# float.net
KiCad netlist of a schematic drawn in Altium Designer
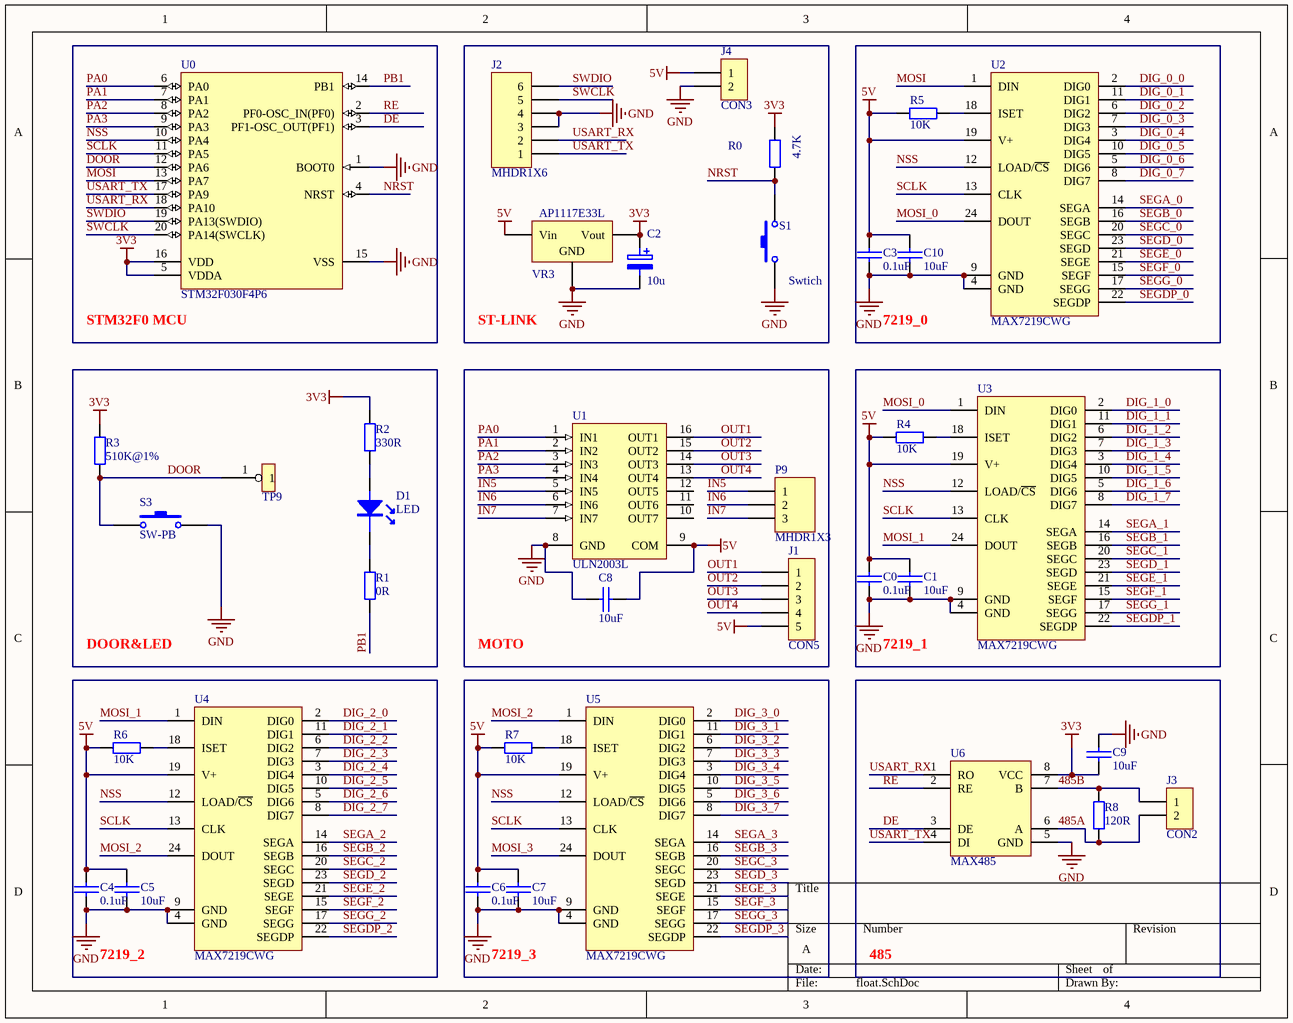
[diagram p0: float.SchDoc]

(export (version "E")
  (design (tool "Eeschema 10.0.6"))
  (components
    (comp (ref "C0")
      (value "0.1uF")
      (footprint "0603C")
      (description "Capacitor")
      (libsource (lib "Miscellaneous Devices") (part "CAP"))
    )
    (comp (ref "C1")
      (value "10uF")
      (footprint "0603C")
      (description "Capacitor")
      (libsource (lib "Miscellaneous Devices") (part "CAP"))
    )
    (comp (ref "C2") (value "10u") (footprint "LC-CASE-B_3528") (libsource (lib "*") (part "ELECTRO2")))
    (comp (ref "C3")
      (value "0.1uF")
      (footprint "0603C")
      (description "Capacitor")
      (libsource (lib "Miscellaneous Devices") (part "CAP"))
    )
    (comp (ref "C4")
      (value "0.1uF")
      (footprint "0603C")
      (description "Capacitor")
      (libsource (lib "Miscellaneous Devices") (part "CAP"))
    )
    (comp (ref "C5")
      (value "10uF")
      (footprint "0603C")
      (description "Capacitor")
      (libsource (lib "Miscellaneous Devices") (part "CAP"))
    )
    (comp (ref "C6")
      (value "0.1uF")
      (footprint "0603C")
      (description "Capacitor")
      (libsource (lib "Miscellaneous Devices") (part "CAP"))
    )
    (comp (ref "C7")
      (value "10uF")
      (footprint "0603C")
      (description "Capacitor")
      (libsource (lib "Miscellaneous Devices") (part "CAP"))
    )
    (comp (ref "C8")
      (value "10uF")
      (footprint "0603C")
      (description "Capacitor")
      (libsource (lib "Miscellaneous Devices") (part "CAP"))
    )
    (comp (ref "C9")
      (value "10uF")
      (footprint "0603C")
      (description "Capacitor")
      (libsource (lib "Miscellaneous Devices") (part "CAP"))
    )
    (comp (ref "C10")
      (value "10uF")
      (footprint "0603C")
      (description "Capacitor")
      (libsource (lib "Miscellaneous Devices") (part "CAP"))
    )
    (comp (ref "D1")
      (value "LED")
      (footprint "LC-0603_LED_S1")
      (libsource (lib "BASIC Devices") (part "LED"))
    )
    (comp (ref "J1")
      (value "CON5")
      (footprint "HDR1X5")
      (description "Connector")
      (libsource (lib "插件") (part "CON5"))
    )
    (comp (ref "J2")
      (value "MHDR1X6")
      (footprint "Miscellaneous Connectors:HDR1X6")
      (description "Header, 6-Pin")
      (fields (field (name "PUBLISHER") "Altium Limited"))
      (libsource (lib "Miscellaneous Connectors") (part "MHDR1X6"))
    )
    (comp (ref "J3")
      (value "CON2")
      (footprint "HDR1X2")
      (description "Connector")
      (libsource (lib "Miscellaneous Devices") (part "CON2"))
    )
    (comp (ref "J4")
      (value "CON3")
      (footprint "HDR1X2")
      (description "Connector")
      (libsource (lib "Miscellaneous Devices") (part "CON2"))
    )
    (comp (ref "P9")
      (value "MHDR1X3")
      (footprint "HDR1X3")
      (description "Header, 3-Pin")
      (fields (field (name "PUBLISHER") "Altium Limited"))
      (libsource (lib "Miscellaneous Connectors") (part "MHDR1X3"))
    )
    (comp (ref "R0")
      (value "4.7K")
      (footprint "0603R")
      (description "Resistor")
      (fields (field (name "Comment") "RES") (field (name "PUBLISHER") "Altium Limited"))
      (libsource (lib "") (part "Res2_1"))
    )
    (comp (ref "R1")
      (value "0R")
      (footprint "0603R")
      (description "贴片电阻")
      (fields (field (name "Comment") "Res1") (field (name "PUBLISHER") "Altium Limited"))
      (libsource (lib "Fszhang") (part "Res1"))
    )
    (comp (ref "R2")
      (value "330R")
      (footprint "0603R")
      (description "贴片电阻")
      (fields (field (name "Comment") "Res1") (field (name "PUBLISHER") "Altium Limited"))
      (libsource (lib "Fszhang") (part "Res1"))
    )
    (comp (ref "R3")
      (value "510K@1%")
      (footprint "0603R")
      (description "Resistor")
      (fields (field (name "Comment") "Res") (field (name "PUBLISHER") "Altium Limited"))
      (libsource (lib "") (part "Res2_3"))
    )
    (comp (ref "R4")
      (value "10K")
      (footprint "0603R")
      (description "Resistor")
      (fields (field (name "Comment") "RES") (field (name "PUBLISHER") "Altium Limited"))
      (libsource (lib "Miscellaneous Devices") (part "Res2"))
    )
    (comp (ref "R5")
      (value "10K")
      (footprint "0603R")
      (description "Resistor")
      (fields (field (name "Comment") "RES") (field (name "PUBLISHER") "Altium Limited"))
      (libsource (lib "Miscellaneous Devices") (part "Res2"))
    )
    (comp (ref "R6")
      (value "10K")
      (footprint "0603R")
      (description "Resistor")
      (fields (field (name "Comment") "RES") (field (name "PUBLISHER") "Altium Limited"))
      (libsource (lib "Miscellaneous Devices") (part "Res2"))
    )
    (comp (ref "R7")
      (value "10K")
      (footprint "0603R")
      (description "Resistor")
      (fields (field (name "Comment") "RES") (field (name "PUBLISHER") "Altium Limited"))
      (libsource (lib "Miscellaneous Devices") (part "Res2"))
    )
    (comp (ref "R8")
      (value "120R")
      (footprint "0603R")
      (description "Resistor")
      (fields (field (name "Comment") "RES") (field (name "PUBLISHER") "Altium Limited"))
      (libsource (lib "") (part "Res2_2"))
    )
    (comp (ref "S1")
      (value "Swtich")
      (footprint "KEY_M")
      (description "Switch")
      (fields (field (name "PUBLISHER") "Altium Limited"))
      (libsource (lib "connectors") (part "SW-PB"))
    )
    (comp (ref "S3")
      (value "SW-PB")
      (footprint "reed_switch")
      (description "Switch")
      (fields (field (name "PUBLISHER") "Altium Limited"))
      (libsource (lib "connectors") (part "SW-PB"))
    )
    (comp (ref "TP9") (value "TP") (footprint "TP1") (libsource (lib "devices") (part "TP")))
    (comp (ref "U0")
      (value "STM32F030F4P6")
      (footprint "STM-TSSOP20_L")
      (libsource (lib "STMicroelectronics STM32 F0") (part "STM32F030F4P6"))
    )
    (comp (ref "U1")
      (value "ULN2003L")
      (footprint "NSO16_M")
      (description "驱动芯片")
      (fields (field (name "PUBLISHER") "Altium Limited"))
      (libsource (lib "Fszhang") (part "ULN2003L"))
    )
    (comp (ref "U2")
      (value "MAX7219CWG")
      (footprint "SO-24W")
      (description "CI-MAX7219CWG")
      (libsource (lib "IC(1)") (part "MAX7219CWG"))
    )
    (comp (ref "U3")
      (value "MAX7219CWG")
      (footprint "SO-24W")
      (description "CI-MAX7219CWG")
      (libsource (lib "IC(1)") (part "MAX7219CWG"))
    )
    (comp (ref "U4")
      (value "MAX7219CWG")
      (footprint "SO-24W")
      (description "CI-MAX7219CWG")
      (libsource (lib "IC(1)") (part "MAX7219CWG"))
    )
    (comp (ref "U5")
      (value "MAX7219CWG")
      (footprint "SO-24W")
      (description "CI-MAX7219CWG")
      (libsource (lib "IC(1)") (part "MAX7219CWG"))
    )
    (comp (ref "U6")
      (value "MAX485")
      (footprint "NSO8_N")
      (description "485总线芯片")
      (libsource (lib "Fszhang") (part "SP3485"))
    )
    (comp (ref "VR3")
      (value "AP1117E33L")
      (footprint "LC-SOT-223")
      (description "Voltage Regulator")
      (fields (field (name "PUBLISHER") "Altium Limited"))
      (libsource (lib "在线监测仪-02") (part "Volt Reg"))
    )
  )
  (nets
    (net (code "1") (name "/485A") (class "Default")
      (node (ref "J3") (pin "2") (pinfunction "2_2") (pintype "passive"))
      (node (ref "R8") (pin "1") (pinfunction "1_1") (pintype "passive"))
      (node (ref "U6") (pin "6") (pinfunction "A_6") (pintype "passive"))
    )
    (net (code "2") (name "/485B") (class "Default")
      (node (ref "J3") (pin "1") (pinfunction "1_1") (pintype "passive"))
      (node (ref "R8") (pin "2") (pinfunction "2_2") (pintype "passive"))
      (node (ref "U6") (pin "7") (pinfunction "B_7") (pintype "passive"))
    )
    (net (code "3") (name "/DE") (class "Default")
      (node (ref "U0") (pin "3") (pinfunction "PF1-OSC_OUT(PF1)_3") (pintype "bidirectional"))
      (node (ref "U6") (pin "3") (pinfunction "DE_3") (pintype "passive"))
    )
    (net (code "4") (name "/DIG_0_0") (class "Default")
      (node (ref "U2") (pin "2") (pinfunction "DIG0_2") (pintype "passive"))
    )
    (net (code "5") (name "/DIG_0_1") (class "Default")
      (node (ref "U2") (pin "11") (pinfunction "DIG1_11") (pintype "passive"))
    )
    (net (code "6") (name "/DIG_0_2") (class "Default")
      (node (ref "U2") (pin "6") (pinfunction "DIG2_6") (pintype "passive"))
    )
    (net (code "7") (name "/DIG_0_3") (class "Default")
      (node (ref "U2") (pin "7") (pinfunction "DIG3_7") (pintype "passive"))
    )
    (net (code "8") (name "/DIG_0_4") (class "Default")
      (node (ref "U2") (pin "3") (pinfunction "DIG4_3") (pintype "passive"))
    )
    (net (code "9") (name "/DIG_0_5") (class "Default")
      (node (ref "U2") (pin "10") (pinfunction "DIG5_10") (pintype "passive"))
    )
    (net (code "10") (name "/DIG_0_6") (class "Default")
      (node (ref "U2") (pin "5") (pinfunction "DIG6_5") (pintype "passive"))
    )
    (net (code "11") (name "/DIG_0_7") (class "Default")
      (node (ref "U2") (pin "8") (pinfunction "DIG7_8") (pintype "passive"))
    )
    (net (code "12") (name "/DIG_1_0") (class "Default")
      (node (ref "U3") (pin "2") (pinfunction "DIG0_2") (pintype "passive"))
    )
    (net (code "13") (name "/DIG_1_1") (class "Default")
      (node (ref "U3") (pin "11") (pinfunction "DIG1_11") (pintype "passive"))
    )
    (net (code "14") (name "/DIG_1_2") (class "Default")
      (node (ref "U3") (pin "6") (pinfunction "DIG2_6") (pintype "passive"))
    )
    (net (code "15") (name "/DIG_1_3") (class "Default")
      (node (ref "U3") (pin "7") (pinfunction "DIG3_7") (pintype "passive"))
    )
    (net (code "16") (name "/DIG_1_4") (class "Default")
      (node (ref "U3") (pin "3") (pinfunction "DIG4_3") (pintype "passive"))
    )
    (net (code "17") (name "/DIG_1_5") (class "Default")
      (node (ref "U3") (pin "10") (pinfunction "DIG5_10") (pintype "passive"))
    )
    (net (code "18") (name "/DIG_1_6") (class "Default")
      (node (ref "U3") (pin "5") (pinfunction "DIG6_5") (pintype "passive"))
    )
    (net (code "19") (name "/DIG_1_7") (class "Default")
      (node (ref "U3") (pin "8") (pinfunction "DIG7_8") (pintype "passive"))
    )
    (net (code "20") (name "/DIG_2_0") (class "Default")
      (node (ref "U4") (pin "2") (pinfunction "DIG0_2") (pintype "passive"))
    )
    (net (code "21") (name "/DIG_2_1") (class "Default")
      (node (ref "U4") (pin "11") (pinfunction "DIG1_11") (pintype "passive"))
    )
    (net (code "22") (name "/DIG_2_2") (class "Default")
      (node (ref "U4") (pin "6") (pinfunction "DIG2_6") (pintype "passive"))
    )
    (net (code "23") (name "/DIG_2_3") (class "Default")
      (node (ref "U4") (pin "7") (pinfunction "DIG3_7") (pintype "passive"))
    )
    (net (code "24") (name "/DIG_2_4") (class "Default")
      (node (ref "U4") (pin "3") (pinfunction "DIG4_3") (pintype "passive"))
    )
    (net (code "25") (name "/DIG_2_5") (class "Default")
      (node (ref "U4") (pin "10") (pinfunction "DIG5_10") (pintype "passive"))
    )
    (net (code "26") (name "/DIG_2_6") (class "Default")
      (node (ref "U4") (pin "5") (pinfunction "DIG6_5") (pintype "passive"))
    )
    (net (code "27") (name "/DIG_2_7") (class "Default")
      (node (ref "U4") (pin "8") (pinfunction "DIG7_8") (pintype "passive"))
    )
    (net (code "28") (name "/DIG_3_0") (class "Default")
      (node (ref "U5") (pin "2") (pinfunction "DIG0_2") (pintype "passive"))
    )
    (net (code "29") (name "/DIG_3_1") (class "Default")
      (node (ref "U5") (pin "11") (pinfunction "DIG1_11") (pintype "passive"))
    )
    (net (code "30") (name "/DIG_3_2") (class "Default")
      (node (ref "U5") (pin "6") (pinfunction "DIG2_6") (pintype "passive"))
    )
    (net (code "31") (name "/DIG_3_3") (class "Default")
      (node (ref "U5") (pin "7") (pinfunction "DIG3_7") (pintype "passive"))
    )
    (net (code "32") (name "/DIG_3_4") (class "Default")
      (node (ref "U5") (pin "3") (pinfunction "DIG4_3") (pintype "passive"))
    )
    (net (code "33") (name "/DIG_3_5") (class "Default")
      (node (ref "U5") (pin "10") (pinfunction "DIG5_10") (pintype "passive"))
    )
    (net (code "34") (name "/DIG_3_6") (class "Default")
      (node (ref "U5") (pin "5") (pinfunction "DIG6_5") (pintype "passive"))
    )
    (net (code "35") (name "/DIG_3_7") (class "Default")
      (node (ref "U5") (pin "8") (pinfunction "DIG7_8") (pintype "passive"))
    )
    (net (code "36") (name "/DOOR") (class "Default")
      (node (ref "R3") (pin "2") (pinfunction "2_2") (pintype "passive"))
      (node (ref "S3") (pin "1") (pinfunction "1_1") (pintype "passive"))
      (node (ref "TP9") (pin "1") (pinfunction "1_1") (pintype "passive"))
      (node (ref "U0") (pin "12") (pinfunction "PA6_12") (pintype "bidirectional"))
    )
    (net (code "37") (name "/IN5") (class "Default")
      (node (ref "P9") (pin "1") (pinfunction "1_1") (pintype "passive"))
      (node (ref "U1") (pin "5") (pinfunction "IN5_5") (pintype "input"))
    )
    (net (code "38") (name "/IN6") (class "Default")
      (node (ref "P9") (pin "2") (pinfunction "2_2") (pintype "passive"))
      (node (ref "U1") (pin "6") (pinfunction "IN6_6") (pintype "input"))
    )
    (net (code "39") (name "/IN7") (class "Default")
      (node (ref "P9") (pin "3") (pinfunction "3_3") (pintype "passive"))
      (node (ref "U1") (pin "7") (pinfunction "IN7_7") (pintype "input"))
    )
    (net (code "40") (name "/MOSI") (class "Default")
      (node (ref "U0") (pin "13") (pinfunction "PA7_13") (pintype "bidirectional"))
      (node (ref "U2") (pin "1") (pinfunction "DIN_1") (pintype "passive"))
    )
    (net (code "41") (name "/MOSI_0") (class "Default")
      (node (ref "U2") (pin "24") (pinfunction "DOUT_24") (pintype "passive"))
      (node (ref "U3") (pin "1") (pinfunction "DIN_1") (pintype "passive"))
    )
    (net (code "42") (name "/MOSI_1") (class "Default")
      (node (ref "U3") (pin "24") (pinfunction "DOUT_24") (pintype "passive"))
      (node (ref "U4") (pin "1") (pinfunction "DIN_1") (pintype "passive"))
    )
    (net (code "43") (name "/MOSI_2") (class "Default")
      (node (ref "U4") (pin "24") (pinfunction "DOUT_24") (pintype "passive"))
      (node (ref "U5") (pin "1") (pinfunction "DIN_1") (pintype "passive"))
    )
    (net (code "44") (name "/MOSI_3") (class "Default")
      (node (ref "U5") (pin "24") (pinfunction "DOUT_24") (pintype "passive"))
    )
    (net (code "45") (name "/NRST") (class "Default")
      (node (ref "R0") (pin "2") (pinfunction "2_2") (pintype "passive"))
      (node (ref "S1") (pin "2") (pinfunction "2_2") (pintype "passive"))
      (node (ref "U0") (pin "4") (pinfunction "NRST_4") (pintype "bidirectional"))
    )
    (net (code "46") (name "/NSS") (class "Default")
      (node (ref "U0") (pin "10") (pinfunction "PA4_10") (pintype "bidirectional"))
      (node (ref "U2") (pin "12") (pinfunction "LOAD/~{CS}_12") (pintype "passive"))
      (node (ref "U3") (pin "12") (pinfunction "LOAD/~{CS}_12") (pintype "passive"))
      (node (ref "U4") (pin "12") (pinfunction "LOAD/~{CS}_12") (pintype "passive"))
      (node (ref "U5") (pin "12") (pinfunction "LOAD/~{CS}_12") (pintype "passive"))
    )
    (net (code "47") (name "/OUT1") (class "Default")
      (node (ref "J1") (pin "1") (pinfunction "1_1") (pintype "passive"))
      (node (ref "U1") (pin "16") (pinfunction "OUT1_16") (pintype "open_collector"))
    )
    (net (code "48") (name "/OUT2") (class "Default")
      (node (ref "J1") (pin "2") (pinfunction "2_2") (pintype "passive"))
      (node (ref "U1") (pin "15") (pinfunction "OUT2_15") (pintype "open_collector"))
    )
    (net (code "49") (name "/OUT3") (class "Default")
      (node (ref "J1") (pin "3") (pinfunction "3_3") (pintype "passive"))
      (node (ref "U1") (pin "14") (pinfunction "OUT3_14") (pintype "open_collector"))
    )
    (net (code "50") (name "/OUT4") (class "Default")
      (node (ref "J1") (pin "4") (pinfunction "4_4") (pintype "passive"))
      (node (ref "U1") (pin "13") (pinfunction "OUT4_13") (pintype "open_collector"))
    )
    (net (code "51") (name "/PA0") (class "Default")
      (node (ref "U0") (pin "6") (pinfunction "PA0_6") (pintype "bidirectional"))
      (node (ref "U1") (pin "1") (pinfunction "IN1_1") (pintype "input"))
    )
    (net (code "52") (name "/PA1") (class "Default")
      (node (ref "U0") (pin "7") (pinfunction "PA1_7") (pintype "bidirectional"))
      (node (ref "U1") (pin "2") (pinfunction "IN2_2") (pintype "input"))
    )
    (net (code "53") (name "/PA2") (class "Default")
      (node (ref "U0") (pin "8") (pinfunction "PA2_8") (pintype "bidirectional"))
      (node (ref "U1") (pin "3") (pinfunction "IN3_3") (pintype "input"))
    )
    (net (code "54") (name "/PA3") (class "Default")
      (node (ref "U0") (pin "9") (pinfunction "PA3_9") (pintype "bidirectional"))
      (node (ref "U1") (pin "4") (pinfunction "IN4_4") (pintype "input"))
    )
    (net (code "55") (name "/PB1") (class "Default")
      (node (ref "R1") (pin "2") (pinfunction "2_2") (pintype "passive"))
      (node (ref "U0") (pin "14") (pinfunction "PB1_14") (pintype "bidirectional"))
    )
    (net (code "56") (name "/RE") (class "Default")
      (node (ref "U0") (pin "2") (pinfunction "PF0-OSC_IN(PF0)_2") (pintype "bidirectional"))
      (node (ref "U6") (pin "2") (pinfunction "RE_2") (pintype "passive"))
    )
    (net (code "57") (name "/SCLK") (class "Default")
      (node (ref "U0") (pin "11") (pinfunction "PA5_11") (pintype "bidirectional"))
      (node (ref "U2") (pin "13") (pinfunction "CLK_13") (pintype "passive"))
      (node (ref "U3") (pin "13") (pinfunction "CLK_13") (pintype "passive"))
      (node (ref "U4") (pin "13") (pinfunction "CLK_13") (pintype "passive"))
      (node (ref "U5") (pin "13") (pinfunction "CLK_13") (pintype "passive"))
    )
    (net (code "58") (name "/SEGA_0") (class "Default")
      (node (ref "U2") (pin "14") (pinfunction "SEGA_14") (pintype "passive"))
    )
    (net (code "59") (name "/SEGA_1") (class "Default")
      (node (ref "U3") (pin "14") (pinfunction "SEGA_14") (pintype "passive"))
    )
    (net (code "60") (name "/SEGA_2") (class "Default")
      (node (ref "U4") (pin "14") (pinfunction "SEGA_14") (pintype "passive"))
    )
    (net (code "61") (name "/SEGA_3") (class "Default")
      (node (ref "U5") (pin "14") (pinfunction "SEGA_14") (pintype "passive"))
    )
    (net (code "62") (name "/SEGB_0") (class "Default")
      (node (ref "U2") (pin "16") (pinfunction "SEGB_16") (pintype "passive"))
    )
    (net (code "63") (name "/SEGB_1") (class "Default")
      (node (ref "U3") (pin "16") (pinfunction "SEGB_16") (pintype "passive"))
    )
    (net (code "64") (name "/SEGB_2") (class "Default")
      (node (ref "U4") (pin "16") (pinfunction "SEGB_16") (pintype "passive"))
    )
    (net (code "65") (name "/SEGB_3") (class "Default")
      (node (ref "U5") (pin "16") (pinfunction "SEGB_16") (pintype "passive"))
    )
    (net (code "66") (name "/SEGC_0") (class "Default")
      (node (ref "U2") (pin "20") (pinfunction "SEGC_20") (pintype "passive"))
    )
    (net (code "67") (name "/SEGC_1") (class "Default")
      (node (ref "U3") (pin "20") (pinfunction "SEGC_20") (pintype "passive"))
    )
    (net (code "68") (name "/SEGC_2") (class "Default")
      (node (ref "U4") (pin "20") (pinfunction "SEGC_20") (pintype "passive"))
    )
    (net (code "69") (name "/SEGC_3") (class "Default")
      (node (ref "U5") (pin "20") (pinfunction "SEGC_20") (pintype "passive"))
    )
    (net (code "70") (name "/SEGDP_0") (class "Default")
      (node (ref "U2") (pin "22") (pinfunction "SEGDP_22") (pintype "passive"))
    )
    (net (code "71") (name "/SEGDP_1") (class "Default")
      (node (ref "U3") (pin "22") (pinfunction "SEGDP_22") (pintype "passive"))
    )
    (net (code "72") (name "/SEGDP_2") (class "Default")
      (node (ref "U4") (pin "22") (pinfunction "SEGDP_22") (pintype "passive"))
    )
    (net (code "73") (name "/SEGDP_3") (class "Default")
      (node (ref "U5") (pin "22") (pinfunction "SEGDP_22") (pintype "passive"))
    )
    (net (code "74") (name "/SEGD_0") (class "Default")
      (node (ref "U2") (pin "23") (pinfunction "SEGD_23") (pintype "passive"))
    )
    (net (code "75") (name "/SEGD_1") (class "Default")
      (node (ref "U3") (pin "23") (pinfunction "SEGD_23") (pintype "passive"))
    )
    (net (code "76") (name "/SEGD_2") (class "Default")
      (node (ref "U4") (pin "23") (pinfunction "SEGD_23") (pintype "passive"))
    )
    (net (code "77") (name "/SEGD_3") (class "Default")
      (node (ref "U5") (pin "23") (pinfunction "SEGD_23") (pintype "passive"))
    )
    (net (code "78") (name "/SEGE_0") (class "Default")
      (node (ref "U2") (pin "21") (pinfunction "SEGE_21") (pintype "passive"))
    )
    (net (code "79") (name "/SEGE_1") (class "Default")
      (node (ref "U3") (pin "21") (pinfunction "SEGE_21") (pintype "passive"))
    )
    (net (code "80") (name "/SEGE_2") (class "Default")
      (node (ref "U4") (pin "21") (pinfunction "SEGE_21") (pintype "passive"))
    )
    (net (code "81") (name "/SEGE_3") (class "Default")
      (node (ref "U5") (pin "21") (pinfunction "SEGE_21") (pintype "passive"))
    )
    (net (code "82") (name "/SEGF_0") (class "Default")
      (node (ref "U2") (pin "15") (pinfunction "SEGF_15") (pintype "passive"))
    )
    (net (code "83") (name "/SEGF_1") (class "Default")
      (node (ref "U3") (pin "15") (pinfunction "SEGF_15") (pintype "passive"))
    )
    (net (code "84") (name "/SEGF_2") (class "Default")
      (node (ref "U4") (pin "15") (pinfunction "SEGF_15") (pintype "passive"))
    )
    (net (code "85") (name "/SEGF_3") (class "Default")
      (node (ref "U5") (pin "15") (pinfunction "SEGF_15") (pintype "passive"))
    )
    (net (code "86") (name "/SEGG_0") (class "Default")
      (node (ref "U2") (pin "17") (pinfunction "SEGG_17") (pintype "passive"))
    )
    (net (code "87") (name "/SEGG_1") (class "Default")
      (node (ref "U3") (pin "17") (pinfunction "SEGG_17") (pintype "passive"))
    )
    (net (code "88") (name "/SEGG_2") (class "Default")
      (node (ref "U4") (pin "17") (pinfunction "SEGG_17") (pintype "passive"))
    )
    (net (code "89") (name "/SEGG_3") (class "Default")
      (node (ref "U5") (pin "17") (pinfunction "SEGG_17") (pintype "passive"))
    )
    (net (code "90") (name "/SWCLK") (class "Default")
      (node (ref "J2") (pin "5") (pinfunction "5_5") (pintype "passive"))
      (node (ref "U0") (pin "20") (pinfunction "PA14(SWCLK)_20") (pintype "bidirectional"))
    )
    (net (code "91") (name "/SWDIO") (class "Default")
      (node (ref "J2") (pin "6") (pinfunction "6_6") (pintype "passive"))
      (node (ref "U0") (pin "19") (pinfunction "PA13(SWDIO)_19") (pintype "bidirectional"))
    )
    (net (code "92") (name "/USART_RX") (class "Default")
      (node (ref "J2") (pin "2") (pinfunction "2_2") (pintype "passive"))
      (node (ref "U0") (pin "18") (pinfunction "PA10_18") (pintype "bidirectional"))
      (node (ref "U6") (pin "1") (pinfunction "RO_1") (pintype "passive"))
    )
    (net (code "93") (name "/USART_TX") (class "Default")
      (node (ref "J2") (pin "1") (pinfunction "1_1") (pintype "passive"))
      (node (ref "U0") (pin "17") (pinfunction "PA9_17") (pintype "bidirectional"))
      (node (ref "U6") (pin "4") (pinfunction "DI_4") (pintype "passive"))
    )
    (net (code "94") (name "3V3") (class "Default")
      (node (ref "C2") (pin "1") (pintype "passive"))
      (node (ref "C9") (pin "1") (pinfunction "1_1") (pintype "passive"))
      (node (ref "R0") (pin "1") (pinfunction "1_1") (pintype "passive"))
      (node (ref "R2") (pin "1") (pinfunction "1_1") (pintype "passive"))
      (node (ref "R3") (pin "1") (pinfunction "1_1") (pintype "passive"))
      (node (ref "U0") (pin "16") (pinfunction "VDD_16") (pintype "power_in"))
      (node (ref "U0") (pin "5") (pinfunction "VDDA_5") (pintype "power_in"))
      (node (ref "U6") (pin "8") (pinfunction "VCC_8") (pintype "passive"))
      (node (ref "VR3") (pin "2") (pinfunction "Vout_2") (pintype "passive"))
    )
    (net (code "95") (name "5V") (class "Default")
      (node (ref "C0") (pin "2") (pinfunction "2_2") (pintype "passive"))
      (node (ref "C1") (pin "2") (pinfunction "2_2") (pintype "passive"))
      (node (ref "C10") (pin "2") (pinfunction "2_2") (pintype "passive"))
      (node (ref "C3") (pin "2") (pinfunction "2_2") (pintype "passive"))
      (node (ref "C4") (pin "2") (pinfunction "2_2") (pintype "passive"))
      (node (ref "C5") (pin "2") (pinfunction "2_2") (pintype "passive"))
      (node (ref "C6") (pin "2") (pinfunction "2_2") (pintype "passive"))
      (node (ref "C7") (pin "2") (pinfunction "2_2") (pintype "passive"))
      (node (ref "C8") (pin "2") (pinfunction "2_2") (pintype "passive"))
      (node (ref "J1") (pin "5") (pinfunction "5_5") (pintype "passive"))
      (node (ref "J4") (pin "1") (pinfunction "1_1") (pintype "passive"))
      (node (ref "R4") (pin "1") (pinfunction "1_1") (pintype "passive"))
      (node (ref "R5") (pin "1") (pinfunction "1_1") (pintype "passive"))
      (node (ref "R6") (pin "1") (pinfunction "1_1") (pintype "passive"))
      (node (ref "R7") (pin "1") (pinfunction "1_1") (pintype "passive"))
      (node (ref "U1") (pin "9") (pinfunction "COM_9") (pintype "passive"))
      (node (ref "U2") (pin "19") (pinfunction "V+_19") (pintype "power_in"))
      (node (ref "U3") (pin "19") (pinfunction "V+_19") (pintype "power_in"))
      (node (ref "U4") (pin "19") (pinfunction "V+_19") (pintype "power_in"))
      (node (ref "U5") (pin "19") (pinfunction "V+_19") (pintype "power_in"))
      (node (ref "VR3") (pin "3") (pinfunction "Vin_3") (pintype "passive"))
    )
    (net (code "96") (name "GND") (class "Default")
      (node (ref "C0") (pin "1") (pinfunction "1_1") (pintype "passive"))
      (node (ref "C1") (pin "1") (pinfunction "1_1") (pintype "passive"))
      (node (ref "C10") (pin "1") (pinfunction "1_1") (pintype "passive"))
      (node (ref "C2") (pin "2") (pintype "passive"))
      (node (ref "C3") (pin "1") (pinfunction "1_1") (pintype "passive"))
      (node (ref "C4") (pin "1") (pinfunction "1_1") (pintype "passive"))
      (node (ref "C5") (pin "1") (pinfunction "1_1") (pintype "passive"))
      (node (ref "C6") (pin "1") (pinfunction "1_1") (pintype "passive"))
      (node (ref "C7") (pin "1") (pinfunction "1_1") (pintype "passive"))
      (node (ref "C8") (pin "1") (pinfunction "1_1") (pintype "passive"))
      (node (ref "C9") (pin "2") (pinfunction "2_2") (pintype "passive"))
      (node (ref "J2") (pin "3") (pinfunction "3_3") (pintype "passive"))
      (node (ref "J2") (pin "4") (pinfunction "4_4") (pintype "passive"))
      (node (ref "J4") (pin "2") (pinfunction "2_2") (pintype "passive"))
      (node (ref "S1") (pin "1") (pinfunction "1_1") (pintype "passive"))
      (node (ref "S3") (pin "2") (pinfunction "2_2") (pintype "passive"))
      (node (ref "U0") (pin "1") (pinfunction "BOOT0_1") (pintype "input"))
      (node (ref "U0") (pin "15") (pinfunction "VSS_15") (pintype "power_in"))
      (node (ref "U1") (pin "8") (pinfunction "GND_8") (pintype "power_in"))
      (node (ref "U2") (pin "4") (pinfunction "GND_4") (pintype "power_in"))
      (node (ref "U2") (pin "9") (pinfunction "GND_9") (pintype "power_in"))
      (node (ref "U3") (pin "4") (pinfunction "GND_4") (pintype "power_in"))
      (node (ref "U3") (pin "9") (pinfunction "GND_9") (pintype "power_in"))
      (node (ref "U4") (pin "4") (pinfunction "GND_4") (pintype "power_in"))
      (node (ref "U4") (pin "9") (pinfunction "GND_9") (pintype "power_in"))
      (node (ref "U5") (pin "4") (pinfunction "GND_4") (pintype "power_in"))
      (node (ref "U5") (pin "9") (pinfunction "GND_9") (pintype "power_in"))
      (node (ref "U6") (pin "5") (pinfunction "GND_5") (pintype "passive"))
      (node (ref "VR3") (pin "1") (pinfunction "GND_1") (pintype "passive"))
    )
    (net (code "97") (name "Net-(D1-PadA)") (class "Default")
      (node (ref "D1") (pin "A") (pinfunction "A_A") (pintype "passive"))
      (node (ref "R2") (pin "2") (pinfunction "2_2") (pintype "passive"))
    )
    (net (code "98") (name "Net-(D1-PadK)") (class "Default")
      (node (ref "D1") (pin "K") (pinfunction "K_K") (pintype "passive"))
      (node (ref "R1") (pin "1") (pinfunction "1_1") (pintype "passive"))
    )
    (net (code "99") (name "Net-(U2-ISET)") (class "Default")
      (node (ref "R5") (pin "2") (pinfunction "2_2") (pintype "passive"))
      (node (ref "U2") (pin "18") (pinfunction "ISET_18") (pintype "passive"))
    )
    (net (code "100") (name "Net-(U3-ISET)") (class "Default")
      (node (ref "R4") (pin "2") (pinfunction "2_2") (pintype "passive"))
      (node (ref "U3") (pin "18") (pinfunction "ISET_18") (pintype "passive"))
    )
    (net (code "101") (name "Net-(U4-ISET)") (class "Default")
      (node (ref "R6") (pin "2") (pinfunction "2_2") (pintype "passive"))
      (node (ref "U4") (pin "18") (pinfunction "ISET_18") (pintype "passive"))
    )
    (net (code "102") (name "Net-(U5-ISET)") (class "Default")
      (node (ref "R7") (pin "2") (pinfunction "2_2") (pintype "passive"))
      (node (ref "U5") (pin "18") (pinfunction "ISET_18") (pintype "passive"))
    )
    (net (code "103") (name "unconnected-(U1-OUT5-Pad12)") (class "Default")
      (node (ref "U1") (pin "12") (pinfunction "OUT5_12") (pintype "open_collector"))
    )
    (net (code "104") (name "unconnected-(U1-OUT6-Pad11)") (class "Default")
      (node (ref "U1") (pin "11") (pinfunction "OUT6_11") (pintype "open_collector"))
    )
    (net (code "105") (name "unconnected-(U1-OUT7-Pad10)") (class "Default")
      (node (ref "U1") (pin "10") (pinfunction "OUT7_10") (pintype "open_collector"))
    )
  )
)
